# Clock.net
KiCad netlist of a schematic drawn in Altium Designer
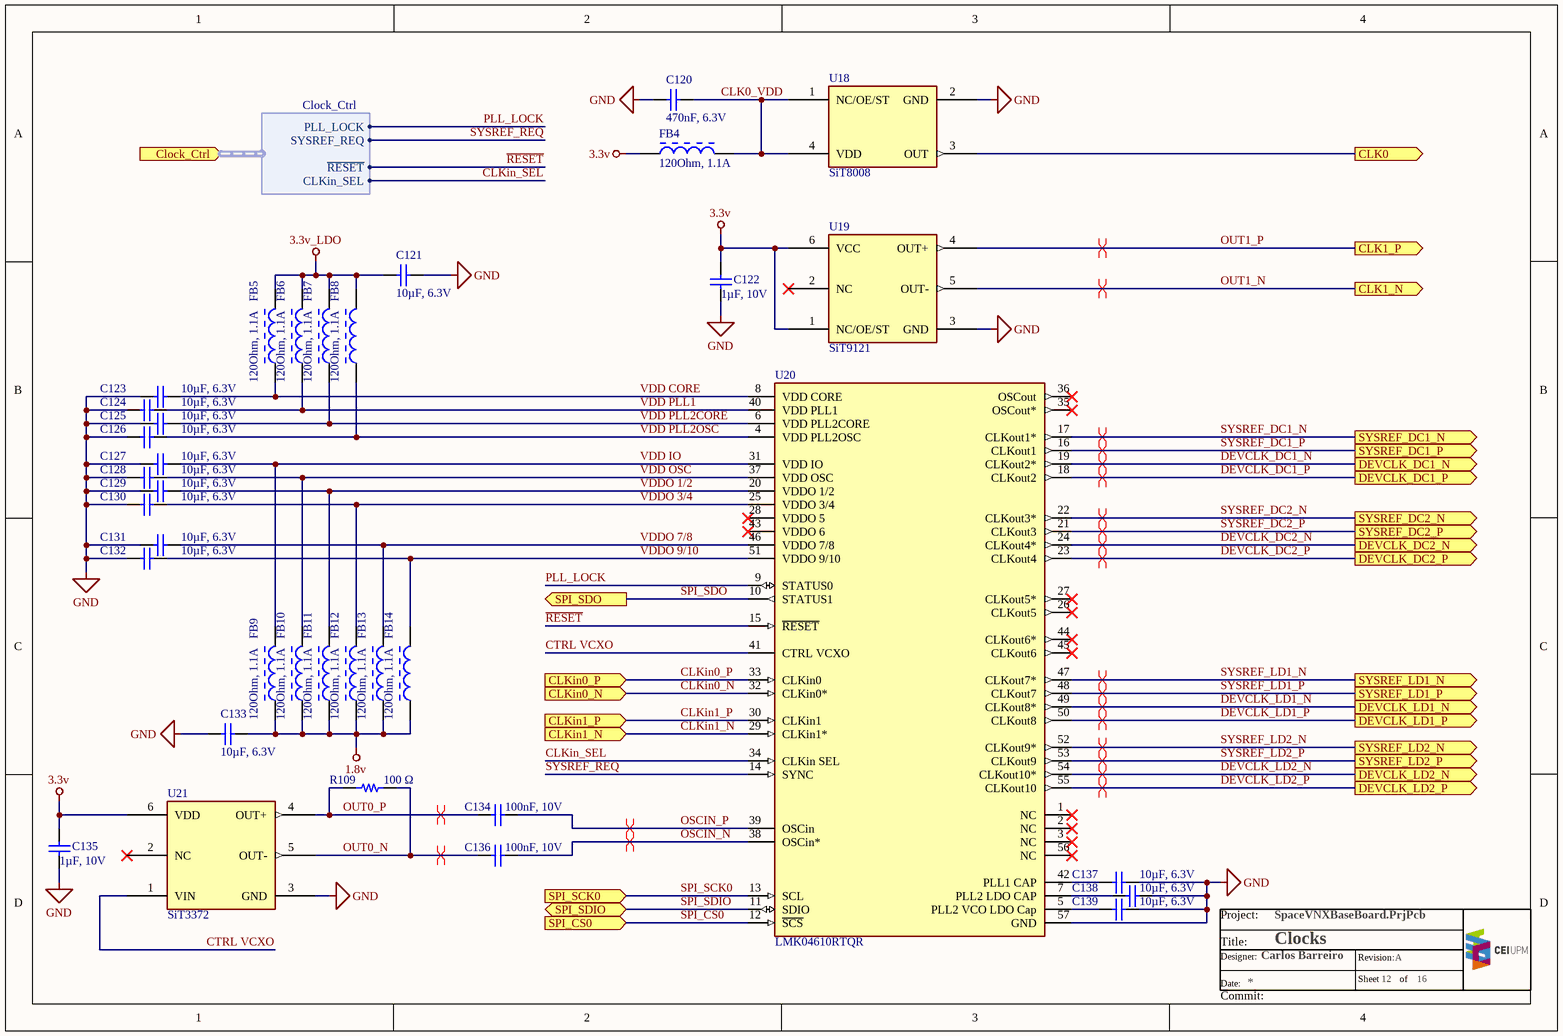
[diagram p0: Clock.SchDoc]

(export (version "E")
  (design (tool "Eeschema 10.0.6"))
  (components
    (comp (ref "C120")
      (value "470nF, 6.3V")
      (footprint "WURTH_WCAP-CSGP_0402")
      (description "WCAP-CSGP Multilayer Ceramic Chip Capacitor, General Purpose, size 0402, X5R, 470nF, 6.3V")
      (fields
        (field (name "MANUFACTURER PART NUMBER") "885012105004")
        (field (name "MANUFACTURER") "Wurth Elektronik")
      )
      (libsource (lib "SpaceVNX") (part "885012105004"))
    )
    (comp (ref "C121")
      (value "10µF, 6.3V")
      (footprint "WURTH_WCAP-CSGP_0402")
      (description "WCAP-CSGP Multilayer Ceramic Chip Capacitor, General Purpose, size 0402, X5R, 10uF, 6.3V")
      (fields
        (field (name "MANUFACTURER PART NUMBER") "885012105020")
        (field (name "MANUFACTURER") "Wurth Elektronik")
      )
      (libsource (lib "SpaceVNX") (part "885012105020"))
    )
    (comp (ref "C122")
      (value "1µF, 10V")
      (footprint "WURTH_WCAP-CSGP_0402")
      (description "WCAP-CSGP Multilayer Ceramic Chip Capacitor, General Purpose, size 0402, X5R, 1uF, 10V")
      (fields
        (field (name "MANUFACTURER PART NUMBER") "885012105012")
        (field (name "MANUFACTURER") "Wurth Elektronik")
      )
      (libsource (lib "SpaceVNX") (part "885012105012"))
    )
    (comp (ref "C123")
      (value "10µF, 6.3V")
      (footprint "WURTH_WCAP-CSGP_0402")
      (description "WCAP-CSGP Multilayer Ceramic Chip Capacitor, General Purpose, size 0402, X5R, 10uF, 6.3V")
      (fields
        (field (name "MANUFACTURER PART NUMBER") "885012105020")
        (field (name "MANUFACTURER") "Wurth Elektronik")
      )
      (libsource (lib "SpaceVNX") (part "885012105020"))
    )
    (comp (ref "C124")
      (value "10µF, 6.3V")
      (footprint "WURTH_WCAP-CSGP_0402")
      (description "WCAP-CSGP Multilayer Ceramic Chip Capacitor, General Purpose, size 0402, X5R, 10uF, 6.3V")
      (fields
        (field (name "MANUFACTURER PART NUMBER") "885012105020")
        (field (name "MANUFACTURER") "Wurth Elektronik")
      )
      (libsource (lib "SpaceVNX") (part "885012105020"))
    )
    (comp (ref "C125")
      (value "10µF, 6.3V")
      (footprint "WURTH_WCAP-CSGP_0402")
      (description "WCAP-CSGP Multilayer Ceramic Chip Capacitor, General Purpose, size 0402, X5R, 10uF, 6.3V")
      (fields
        (field (name "MANUFACTURER PART NUMBER") "885012105020")
        (field (name "MANUFACTURER") "Wurth Elektronik")
      )
      (libsource (lib "SpaceVNX") (part "885012105020"))
    )
    (comp (ref "C126")
      (value "10µF, 6.3V")
      (footprint "WURTH_WCAP-CSGP_0402")
      (description "WCAP-CSGP Multilayer Ceramic Chip Capacitor, General Purpose, size 0402, X5R, 10uF, 6.3V")
      (fields
        (field (name "MANUFACTURER PART NUMBER") "885012105020")
        (field (name "MANUFACTURER") "Wurth Elektronik")
      )
      (libsource (lib "SpaceVNX") (part "885012105020"))
    )
    (comp (ref "C127")
      (value "10µF, 6.3V")
      (footprint "WURTH_WCAP-CSGP_0402")
      (description "WCAP-CSGP Multilayer Ceramic Chip Capacitor, General Purpose, size 0402, X5R, 10uF, 6.3V")
      (fields
        (field (name "MANUFACTURER PART NUMBER") "885012105020")
        (field (name "MANUFACTURER") "Wurth Elektronik")
      )
      (libsource (lib "SpaceVNX") (part "885012105020"))
    )
    (comp (ref "C128")
      (value "10µF, 6.3V")
      (footprint "WURTH_WCAP-CSGP_0402")
      (description "WCAP-CSGP Multilayer Ceramic Chip Capacitor, General Purpose, size 0402, X5R, 10uF, 6.3V")
      (fields
        (field (name "MANUFACTURER PART NUMBER") "885012105020")
        (field (name "MANUFACTURER") "Wurth Elektronik")
      )
      (libsource (lib "SpaceVNX") (part "885012105020"))
    )
    (comp (ref "C129")
      (value "10µF, 6.3V")
      (footprint "WURTH_WCAP-CSGP_0402")
      (description "WCAP-CSGP Multilayer Ceramic Chip Capacitor, General Purpose, size 0402, X5R, 10uF, 6.3V")
      (fields
        (field (name "MANUFACTURER PART NUMBER") "885012105020")
        (field (name "MANUFACTURER") "Wurth Elektronik")
      )
      (libsource (lib "SpaceVNX") (part "885012105020"))
    )
    (comp (ref "C130")
      (value "10µF, 6.3V")
      (footprint "WURTH_WCAP-CSGP_0402")
      (description "WCAP-CSGP Multilayer Ceramic Chip Capacitor, General Purpose, size 0402, X5R, 10uF, 6.3V")
      (fields
        (field (name "MANUFACTURER PART NUMBER") "885012105020")
        (field (name "MANUFACTURER") "Wurth Elektronik")
      )
      (libsource (lib "SpaceVNX") (part "885012105020"))
    )
    (comp (ref "C131")
      (value "10µF, 6.3V")
      (footprint "WURTH_WCAP-CSGP_0402")
      (description "WCAP-CSGP Multilayer Ceramic Chip Capacitor, General Purpose, size 0402, X5R, 10uF, 6.3V")
      (fields
        (field (name "MANUFACTURER PART NUMBER") "885012105020")
        (field (name "MANUFACTURER") "Wurth Elektronik")
      )
      (libsource (lib "SpaceVNX") (part "885012105020"))
    )
    (comp (ref "C132")
      (value "10µF, 6.3V")
      (footprint "WURTH_WCAP-CSGP_0402")
      (description "WCAP-CSGP Multilayer Ceramic Chip Capacitor, General Purpose, size 0402, X5R, 10uF, 6.3V")
      (fields
        (field (name "MANUFACTURER PART NUMBER") "885012105020")
        (field (name "MANUFACTURER") "Wurth Elektronik")
      )
      (libsource (lib "SpaceVNX") (part "885012105020"))
    )
    (comp (ref "C133")
      (value "10µF, 6.3V")
      (footprint "WURTH_WCAP-CSGP_0402")
      (description "WCAP-CSGP Multilayer Ceramic Chip Capacitor, General Purpose, size 0402, X5R, 10uF, 6.3V")
      (fields
        (field (name "MANUFACTURER PART NUMBER") "885012105020")
        (field (name "MANUFACTURER") "Wurth Elektronik")
      )
      (libsource (lib "SpaceVNX") (part "885012105020"))
    )
    (comp (ref "C134")
      (value "100nF, 10V")
      (footprint "WURTH_WCAP-CSGP_0402")
      (description "WCAP-CSGP Multilayer Ceramic Chip Capacitor, General Purpose, size 0402, X7R, 100nF, 10V")
      (fields
        (field (name "MANUFACTURER PART NUMBER") "885012205018")
        (field (name "MANUFACTURER") "Wurth Elektronik")
      )
      (libsource (lib "SpaceVNX") (part "885012205018"))
    )
    (comp (ref "C135")
      (value "1µF, 10V")
      (footprint "WURTH_WCAP-CSGP_0402")
      (description "WCAP-CSGP Multilayer Ceramic Chip Capacitor, General Purpose, size 0402, X5R, 1uF, 10V")
      (fields
        (field (name "MANUFACTURER PART NUMBER") "885012105012")
        (field (name "MANUFACTURER") "Wurth Elektronik")
      )
      (libsource (lib "SpaceVNX") (part "885012105012"))
    )
    (comp (ref "C136")
      (value "100nF, 10V")
      (footprint "WURTH_WCAP-CSGP_0402")
      (description "WCAP-CSGP Multilayer Ceramic Chip Capacitor, General Purpose, size 0402, X7R, 100nF, 10V")
      (fields
        (field (name "MANUFACTURER PART NUMBER") "885012205018")
        (field (name "MANUFACTURER") "Wurth Elektronik")
      )
      (libsource (lib "SpaceVNX") (part "885012205018"))
    )
    (comp (ref "C137")
      (value "10µF, 6.3V")
      (footprint "WURTH_WCAP-CSGP_0402")
      (description "WCAP-CSGP Multilayer Ceramic Chip Capacitor, General Purpose, size 0402, X5R, 10uF, 6.3V")
      (fields
        (field (name "MANUFACTURER PART NUMBER") "885012105020")
        (field (name "MANUFACTURER") "Wurth Elektronik")
      )
      (libsource (lib "SpaceVNX") (part "885012105020"))
    )
    (comp (ref "C138")
      (value "10µF, 6.3V")
      (footprint "WURTH_WCAP-CSGP_0402")
      (description "WCAP-CSGP Multilayer Ceramic Chip Capacitor, General Purpose, size 0402, X5R, 10uF, 6.3V")
      (fields
        (field (name "MANUFACTURER PART NUMBER") "885012105020")
        (field (name "MANUFACTURER") "Wurth Elektronik")
      )
      (libsource (lib "SpaceVNX") (part "885012105020"))
    )
    (comp (ref "C139")
      (value "10µF, 6.3V")
      (footprint "WURTH_WCAP-CSGP_0402")
      (description "WCAP-CSGP Multilayer Ceramic Chip Capacitor, General Purpose, size 0402, X5R, 10uF, 6.3V")
      (fields
        (field (name "MANUFACTURER PART NUMBER") "885012105020")
        (field (name "MANUFACTURER") "Wurth Elektronik")
      )
      (libsource (lib "SpaceVNX") (part "885012105020"))
    )
    (comp (ref "FB4")
      (value "120Ohm, 1.1A")
      (footprint "WURTH-CBF_0402")
      (description "WE-CBF SMT EMI Suppression Ferrite Bead, size 0402, 120Ohm, 1.1A")
      (fields
        (field (name "MANUFACTURER PART NUMBER") "74279271")
        (field (name "MANUFACTURER") "Wurth Elektronik")
      )
      (libsource (lib "SpaceVNX") (part "74279271"))
    )
    (comp (ref "FB5")
      (value "120Ohm, 1.1A")
      (footprint "WURTH-CBF_0402")
      (description "WE-CBF SMT EMI Suppression Ferrite Bead, size 0402, 120Ohm, 1.1A")
      (fields
        (field (name "MANUFACTURER PART NUMBER") "74279271")
        (field (name "MANUFACTURER") "Wurth Elektronik")
      )
      (libsource (lib "SpaceVNX") (part "74279271"))
    )
    (comp (ref "FB6")
      (value "120Ohm, 1.1A")
      (footprint "WURTH-CBF_0402")
      (description "WE-CBF SMT EMI Suppression Ferrite Bead, size 0402, 120Ohm, 1.1A")
      (fields
        (field (name "MANUFACTURER PART NUMBER") "74279271")
        (field (name "MANUFACTURER") "Wurth Elektronik")
      )
      (libsource (lib "SpaceVNX") (part "74279271"))
    )
    (comp (ref "FB7")
      (value "120Ohm, 1.1A")
      (footprint "WURTH-CBF_0402")
      (description "WE-CBF SMT EMI Suppression Ferrite Bead, size 0402, 120Ohm, 1.1A")
      (fields
        (field (name "MANUFACTURER PART NUMBER") "74279271")
        (field (name "MANUFACTURER") "Wurth Elektronik")
      )
      (libsource (lib "SpaceVNX") (part "74279271"))
    )
    (comp (ref "FB8")
      (value "120Ohm, 1.1A")
      (footprint "WURTH-CBF_0402")
      (description "WE-CBF SMT EMI Suppression Ferrite Bead, size 0402, 120Ohm, 1.1A")
      (fields
        (field (name "MANUFACTURER PART NUMBER") "74279271")
        (field (name "MANUFACTURER") "Wurth Elektronik")
      )
      (libsource (lib "SpaceVNX") (part "74279271"))
    )
    (comp (ref "FB9")
      (value "120Ohm, 1.1A")
      (footprint "WURTH-CBF_0402")
      (description "WE-CBF SMT EMI Suppression Ferrite Bead, size 0402, 120Ohm, 1.1A")
      (fields
        (field (name "MANUFACTURER PART NUMBER") "74279271")
        (field (name "MANUFACTURER") "Wurth Elektronik")
      )
      (libsource (lib "SpaceVNX") (part "74279271"))
    )
    (comp (ref "FB10")
      (value "120Ohm, 1.1A")
      (footprint "WURTH-CBF_0402")
      (description "WE-CBF SMT EMI Suppression Ferrite Bead, size 0402, 120Ohm, 1.1A")
      (fields
        (field (name "MANUFACTURER PART NUMBER") "74279271")
        (field (name "MANUFACTURER") "Wurth Elektronik")
      )
      (libsource (lib "SpaceVNX") (part "74279271"))
    )
    (comp (ref "FB11")
      (value "120Ohm, 1.1A")
      (footprint "WURTH-CBF_0402")
      (description "WE-CBF SMT EMI Suppression Ferrite Bead, size 0402, 120Ohm, 1.1A")
      (fields
        (field (name "MANUFACTURER PART NUMBER") "74279271")
        (field (name "MANUFACTURER") "Wurth Elektronik")
      )
      (libsource (lib "SpaceVNX") (part "74279271"))
    )
    (comp (ref "FB12")
      (value "120Ohm, 1.1A")
      (footprint "WURTH-CBF_0402")
      (description "WE-CBF SMT EMI Suppression Ferrite Bead, size 0402, 120Ohm, 1.1A")
      (fields
        (field (name "MANUFACTURER PART NUMBER") "74279271")
        (field (name "MANUFACTURER") "Wurth Elektronik")
      )
      (libsource (lib "SpaceVNX") (part "74279271"))
    )
    (comp (ref "FB13")
      (value "120Ohm, 1.1A")
      (footprint "WURTH-CBF_0402")
      (description "WE-CBF SMT EMI Suppression Ferrite Bead, size 0402, 120Ohm, 1.1A")
      (fields
        (field (name "MANUFACTURER PART NUMBER") "74279271")
        (field (name "MANUFACTURER") "Wurth Elektronik")
      )
      (libsource (lib "SpaceVNX") (part "74279271"))
    )
    (comp (ref "FB14")
      (value "120Ohm, 1.1A")
      (footprint "WURTH-CBF_0402")
      (description "WE-CBF SMT EMI Suppression Ferrite Bead, size 0402, 120Ohm, 1.1A")
      (fields
        (field (name "MANUFACTURER PART NUMBER") "74279271")
        (field (name "MANUFACTURER") "Wurth Elektronik")
      )
      (libsource (lib "SpaceVNX") (part "74279271"))
    )
    (comp (ref "R109")
      (value "100 Ω")
      (footprint "PANASONIC_ERJ2G_0402")
      (description "General Purpose Thick Film Chip Resistors")
      (fields (field (name "MANUFACTURER") "Panasonic"))
      (libsource (lib "SpaceVNX") (part "ERJ2GEJ101X"))
    )
    (comp (ref "U18")
      (value "SiT8008")
      (footprint "SiTime_5032_4")
      (libsource (lib "SpaceVNX") (part "SiT8008"))
    )
    (comp (ref "U19")
      (value "SiT9121")
      (footprint "SiTime_5032_6")
      (description "Programmable differential oscillator that supports LVPECL and LVDS output.")
      (libsource (lib "SpaceVNX") (part "SiT9121"))
    )
    (comp (ref "U20")
      (value "LMK04610RTQR")
      (footprint "TEXAS_VQFN56")
      (description "Ultra low-noise and low power JESD204B compliant clock jitter cleaner with dual PLLs.")
      (libsource (lib "SpaceVNX") (part "LMK04610RTQR"))
    )
    (comp (ref "U21")
      (value "SiT3372")
      (footprint "SiTime_5032_6")
      (description "Ultra-low Jitter Differential VCXO.")
      (libsource (lib "SpaceVNX") (part "SiT3372"))
    )
  )
  (nets
    (net (code "2") (name "/CLK0") (class "Default")
      (node (ref "U18") (pin "3") (pinfunction "OUT_3") (pintype "output"))
    )
    (net (code "3") (name "/CLK0_VDD") (class "Default")
      (node (ref "C120") (pin "2") (pinfunction "2_2") (pintype "passive"))
      (node (ref "FB4") (pin "1") (pinfunction "1_1") (pintype "passive"))
      (node (ref "U18") (pin "1") (pinfunction "NC/OE/ST_1") (pintype "passive"))
      (node (ref "U18") (pin "4") (pinfunction "VDD_4") (pintype "passive"))
    )
    (net (code "4") (name "/CLKin0_N") (class "Default")
      (node (ref "U20") (pin "32") (pinfunction "CLKin0*_32") (pintype "input"))
    )
    (net (code "5") (name "/CLKin0_P") (class "Default")
      (node (ref "U20") (pin "33") (pinfunction "CLKin0_33") (pintype "input"))
    )
    (net (code "6") (name "/CLKin1_N") (class "Default")
      (node (ref "U20") (pin "29") (pinfunction "CLKin1*_29") (pintype "input"))
    )
    (net (code "7") (name "/CLKin1_P") (class "Default")
      (node (ref "U20") (pin "30") (pinfunction "CLKin1_30") (pintype "input"))
    )
    (net (code "8") (name "/CLKin_SEL") (class "Default")
      (node (ref "U20") (pin "34") (pinfunction "CLKin_SEL_34") (pintype "input"))
    )
    (net (code "9") (name "/CTRL VCXO") (class "Default")
      (node (ref "U20") (pin "41") (pinfunction "CTRL_VCXO_41") (pintype "power_in"))
      (node (ref "U21") (pin "1") (pinfunction "VIN_1") (pintype "passive"))
    )
    (net (code "10") (name "/DEVCLK_DC1_N") (class "Default")
      (node (ref "U20") (pin "19") (pinfunction "CLKout2*_19") (pintype "output"))
    )
    (net (code "11") (name "/DEVCLK_DC1_P") (class "Default")
      (node (ref "U20") (pin "18") (pinfunction "CLKout2_18") (pintype "output"))
    )
    (net (code "12") (name "/DEVCLK_DC2_N") (class "Default")
      (node (ref "U20") (pin "24") (pinfunction "CLKout4*_24") (pintype "output"))
    )
    (net (code "13") (name "/DEVCLK_DC2_P") (class "Default")
      (node (ref "U20") (pin "23") (pinfunction "CLKout4_23") (pintype "output"))
    )
    (net (code "14") (name "/DEVCLK_LD1_N") (class "Default")
      (node (ref "U20") (pin "49") (pinfunction "CLKout8*_49") (pintype "output"))
    )
    (net (code "15") (name "/DEVCLK_LD1_P") (class "Default")
      (node (ref "U20") (pin "50") (pinfunction "CLKout8_50") (pintype "output"))
    )
    (net (code "16") (name "/DEVCLK_LD2_N") (class "Default")
      (node (ref "U20") (pin "54") (pinfunction "CLKout10*_54") (pintype "output"))
    )
    (net (code "17") (name "/DEVCLK_LD2_P") (class "Default")
      (node (ref "U20") (pin "55") (pinfunction "CLKout10_55") (pintype "output"))
    )
    (net (code "18") (name "/OSCIN_N") (class "Default")
      (node (ref "C136") (pin "2") (pinfunction "2_2") (pintype "passive"))
      (node (ref "U20") (pin "38") (pinfunction "OSCin*_38") (pintype "passive"))
    )
    (net (code "19") (name "/OSCIN_P") (class "Default")
      (node (ref "C134") (pin "2") (pinfunction "2_2") (pintype "passive"))
      (node (ref "U20") (pin "39") (pinfunction "OSCin_39") (pintype "passive"))
    )
    (net (code "20") (name "/OUT0_N") (class "Default")
      (node (ref "C136") (pin "1") (pinfunction "1_1") (pintype "passive"))
      (node (ref "R109") (pin "2") (pinfunction "2_2") (pintype "passive"))
      (node (ref "U21") (pin "5") (pinfunction "OUT-_5") (pintype "output"))
    )
    (net (code "21") (name "/OUT0_P") (class "Default")
      (node (ref "C134") (pin "1") (pinfunction "1_1") (pintype "passive"))
      (node (ref "R109") (pin "1") (pinfunction "1_1") (pintype "passive"))
      (node (ref "U21") (pin "4") (pinfunction "OUT+_4") (pintype "output"))
    )
    (net (code "22") (name "/OUT1_N") (class "Default")
      (node (ref "U19") (pin "5") (pinfunction "OUT-_5") (pintype "output"))
    )
    (net (code "23") (name "/OUT1_P") (class "Default")
      (node (ref "U19") (pin "4") (pinfunction "OUT+_4") (pintype "output"))
    )
    (net (code "24") (name "/PLL_LOCK") (class "Default")
      (node (ref "U20") (pin "9") (pinfunction "STATUS0_9") (pintype "bidirectional"))
    )
    (net (code "25") (name "/SPI_CS0") (class "Default")
      (node (ref "U20") (pin "12") (pinfunction "~{SCS}_12") (pintype "input"))
    )
    (net (code "26") (name "/SPI_SCK0") (class "Default")
      (node (ref "U20") (pin "13") (pinfunction "SCL_13") (pintype "input"))
    )
    (net (code "27") (name "/SPI_SDIO") (class "Default")
      (node (ref "U20") (pin "11") (pinfunction "SDIO_11") (pintype "bidirectional"))
    )
    (net (code "28") (name "/SPI_SDO") (class "Default")
      (node (ref "U20") (pin "10") (pinfunction "STATUS1_10") (pintype "output"))
    )
    (net (code "29") (name "/SYSREF_DC1_N") (class "Default")
      (node (ref "U20") (pin "17") (pinfunction "CLKout1*_17") (pintype "output"))
    )
    (net (code "30") (name "/SYSREF_DC1_P") (class "Default")
      (node (ref "U20") (pin "16") (pinfunction "CLKout1_16") (pintype "output"))
    )
    (net (code "31") (name "/SYSREF_DC2_N") (class "Default")
      (node (ref "U20") (pin "22") (pinfunction "CLKout3*_22") (pintype "output"))
    )
    (net (code "32") (name "/SYSREF_DC2_P") (class "Default")
      (node (ref "U20") (pin "21") (pinfunction "CLKout3_21") (pintype "output"))
    )
    (net (code "33") (name "/SYSREF_LD1_N") (class "Default")
      (node (ref "U20") (pin "47") (pinfunction "CLKout7*_47") (pintype "output"))
    )
    (net (code "34") (name "/SYSREF_LD1_P") (class "Default")
      (node (ref "U20") (pin "48") (pinfunction "CLKout7_48") (pintype "output"))
    )
    (net (code "35") (name "/SYSREF_LD2_N") (class "Default")
      (node (ref "U20") (pin "52") (pinfunction "CLKout9*_52") (pintype "output"))
    )
    (net (code "36") (name "/SYSREF_LD2_P") (class "Default")
      (node (ref "U20") (pin "53") (pinfunction "CLKout9_53") (pintype "output"))
    )
    (net (code "37") (name "/SYSREF_REQ") (class "Default")
      (node (ref "U20") (pin "14") (pinfunction "SYNC_14") (pintype "input"))
    )
    (net (code "38") (name "/VDD CORE") (class "Default")
      (node (ref "C123") (pin "2") (pinfunction "2_2") (pintype "passive"))
      (node (ref "FB5") (pin "2") (pinfunction "2_2") (pintype "passive"))
      (node (ref "U20") (pin "8") (pinfunction "VDD_CORE_8") (pintype "power_in"))
    )
    (net (code "39") (name "/VDD IO") (class "Default")
      (node (ref "C127") (pin "2") (pinfunction "2_2") (pintype "passive"))
      (node (ref "FB9") (pin "1") (pinfunction "1_1") (pintype "passive"))
      (node (ref "U20") (pin "31") (pinfunction "VDD_IO_31") (pintype "power_in"))
    )
    (net (code "40") (name "/VDD OSC") (class "Default")
      (node (ref "C128") (pin "2") (pinfunction "2_2") (pintype "passive"))
      (node (ref "FB10") (pin "1") (pinfunction "1_1") (pintype "passive"))
      (node (ref "U20") (pin "37") (pinfunction "VDD_OSC_37") (pintype "power_in"))
    )
    (net (code "41") (name "/VDD PLL1") (class "Default")
      (node (ref "C124") (pin "2") (pinfunction "2_2") (pintype "passive"))
      (node (ref "FB6") (pin "2") (pinfunction "2_2") (pintype "passive"))
      (node (ref "U20") (pin "40") (pinfunction "VDD_PLL1_40") (pintype "power_in"))
    )
    (net (code "42") (name "/VDD PLL2CORE") (class "Default")
      (node (ref "C125") (pin "2") (pinfunction "2_2") (pintype "passive"))
      (node (ref "FB7") (pin "2") (pinfunction "2_2") (pintype "passive"))
      (node (ref "U20") (pin "6") (pinfunction "VDD_PLL2CORE_6") (pintype "power_in"))
    )
    (net (code "43") (name "/VDD PLL2OSC") (class "Default")
      (node (ref "C126") (pin "2") (pinfunction "2_2") (pintype "passive"))
      (node (ref "FB8") (pin "2") (pinfunction "2_2") (pintype "passive"))
      (node (ref "U20") (pin "4") (pinfunction "VDD_PLL2OSC_4") (pintype "power_in"))
    )
    (net (code "44") (name "/VDDO 1{slash}2") (class "Default")
      (node (ref "C129") (pin "2") (pinfunction "2_2") (pintype "passive"))
      (node (ref "FB11") (pin "1") (pinfunction "1_1") (pintype "passive"))
      (node (ref "U20") (pin "20") (pinfunction "VDDO_1/2_20") (pintype "power_in"))
    )
    (net (code "45") (name "/VDDO 3{slash}4") (class "Default")
      (node (ref "C130") (pin "2") (pinfunction "2_2") (pintype "passive"))
      (node (ref "FB12") (pin "1") (pinfunction "1_1") (pintype "passive"))
      (node (ref "U20") (pin "25") (pinfunction "VDDO_3/4_25") (pintype "power_in"))
    )
    (net (code "46") (name "/VDDO 7{slash}8") (class "Default")
      (node (ref "C131") (pin "2") (pinfunction "2_2") (pintype "passive"))
      (node (ref "FB13") (pin "1") (pinfunction "1_1") (pintype "passive"))
      (node (ref "U20") (pin "46") (pinfunction "VDDO_7/8_46") (pintype "power_in"))
    )
    (net (code "47") (name "/VDDO 9{slash}10") (class "Default")
      (node (ref "C132") (pin "2") (pinfunction "2_2") (pintype "passive"))
      (node (ref "FB14") (pin "1") (pinfunction "1_1") (pintype "passive"))
      (node (ref "U20") (pin "51") (pinfunction "VDDO_9/10_51") (pintype "power_in"))
    )
    (net (code "49") (name "/~{RESET}") (class "Default")
      (node (ref "U20") (pin "15") (pinfunction "~{RESET}_15") (pintype "input"))
    )
    (net (code "50") (name "1.8v") (class "Default")
      (node (ref "C133") (pin "2") (pinfunction "2_2") (pintype "passive"))
      (node (ref "FB10") (pin "2") (pinfunction "2_2") (pintype "passive"))
      (node (ref "FB11") (pin "2") (pinfunction "2_2") (pintype "passive"))
      (node (ref "FB12") (pin "2") (pinfunction "2_2") (pintype "passive"))
      (node (ref "FB13") (pin "2") (pinfunction "2_2") (pintype "passive"))
      (node (ref "FB14") (pin "2") (pinfunction "2_2") (pintype "passive"))
      (node (ref "FB9") (pin "2") (pinfunction "2_2") (pintype "passive"))
    )
    (net (code "51") (name "3.3v") (class "Default")
      (node (ref "C122") (pin "2") (pinfunction "2_2") (pintype "passive"))
      (node (ref "C135") (pin "2") (pinfunction "2_2") (pintype "passive"))
      (node (ref "FB4") (pin "2") (pinfunction "2_2") (pintype "passive"))
      (node (ref "U19") (pin "1") (pinfunction "NC/OE/ST_1") (pintype "passive"))
      (node (ref "U19") (pin "6") (pinfunction "VCC_6") (pintype "passive"))
      (node (ref "U21") (pin "6") (pinfunction "VDD_6") (pintype "passive"))
    )
    (net (code "52") (name "3.3v_LDO") (class "Default")
      (node (ref "C121") (pin "1") (pinfunction "1_1") (pintype "passive"))
      (node (ref "FB5") (pin "1") (pinfunction "1_1") (pintype "passive"))
      (node (ref "FB6") (pin "1") (pinfunction "1_1") (pintype "passive"))
      (node (ref "FB7") (pin "1") (pinfunction "1_1") (pintype "passive"))
      (node (ref "FB8") (pin "1") (pinfunction "1_1") (pintype "passive"))
    )
    (net (code "53") (name "GND") (class "Default")
      (node (ref "C120") (pin "1") (pinfunction "1_1") (pintype "passive"))
      (node (ref "C121") (pin "2") (pinfunction "2_2") (pintype "passive"))
      (node (ref "C122") (pin "1") (pinfunction "1_1") (pintype "passive"))
      (node (ref "C123") (pin "1") (pinfunction "1_1") (pintype "passive"))
      (node (ref "C124") (pin "1") (pinfunction "1_1") (pintype "passive"))
      (node (ref "C125") (pin "1") (pinfunction "1_1") (pintype "passive"))
      (node (ref "C126") (pin "1") (pinfunction "1_1") (pintype "passive"))
      (node (ref "C127") (pin "1") (pinfunction "1_1") (pintype "passive"))
      (node (ref "C128") (pin "1") (pinfunction "1_1") (pintype "passive"))
      (node (ref "C129") (pin "1") (pinfunction "1_1") (pintype "passive"))
      (node (ref "C130") (pin "1") (pinfunction "1_1") (pintype "passive"))
      (node (ref "C131") (pin "1") (pinfunction "1_1") (pintype "passive"))
      (node (ref "C132") (pin "1") (pinfunction "1_1") (pintype "passive"))
      (node (ref "C133") (pin "1") (pinfunction "1_1") (pintype "passive"))
      (node (ref "C135") (pin "1") (pinfunction "1_1") (pintype "passive"))
      (node (ref "C137") (pin "2") (pinfunction "2_2") (pintype "passive"))
      (node (ref "C138") (pin "2") (pinfunction "2_2") (pintype "passive"))
      (node (ref "C139") (pin "2") (pinfunction "2_2") (pintype "passive"))
      (node (ref "U18") (pin "2") (pinfunction "GND_2") (pintype "passive"))
      (node (ref "U19") (pin "3") (pinfunction "GND_3") (pintype "passive"))
      (node (ref "U20") (pin "57") (pinfunction "GND_57") (pintype "power_in"))
      (node (ref "U21") (pin "3") (pinfunction "GND_3") (pintype "passive"))
    )
    (net (code "54") (name "Net-(U20-PLL1_CAP)") (class "Default")
      (node (ref "C137") (pin "1") (pinfunction "1_1") (pintype "passive"))
      (node (ref "U20") (pin "42") (pinfunction "PLL1_CAP_42") (pintype "passive"))
    )
    (net (code "55") (name "Net-(U20-PLL2_LDO_CAP)") (class "Default")
      (node (ref "C138") (pin "1") (pinfunction "1_1") (pintype "passive"))
      (node (ref "U20") (pin "7") (pinfunction "PLL2_LDO_CAP_7") (pintype "power_in"))
    )
    (net (code "56") (name "Net-(U20-PLL2_VCO_LDO_Cap)") (class "Default")
      (node (ref "C139") (pin "1") (pinfunction "1_1") (pintype "passive"))
      (node (ref "U20") (pin "5") (pinfunction "PLL2_VCO_LDO_Cap_5") (pintype "power_in"))
    )
    (net (code "57") (name "unconnected-(U19-NC-Pad2)") (class "Default")
      (node (ref "U19") (pin "2") (pinfunction "NC_2") (pintype "passive+no_connect"))
    )
    (net (code "58") (name "unconnected-(U20-CLKout5*-Pad27)") (class "Default")
      (node (ref "U20") (pin "27") (pinfunction "CLKout5*_27") (pintype "output+no_connect"))
    )
    (net (code "59") (name "unconnected-(U20-CLKout5-Pad26)") (class "Default")
      (node (ref "U20") (pin "26") (pinfunction "CLKout5_26") (pintype "output+no_connect"))
    )
    (net (code "60") (name "unconnected-(U20-CLKout6*-Pad44)") (class "Default")
      (node (ref "U20") (pin "44") (pinfunction "CLKout6*_44") (pintype "output+no_connect"))
    )
    (net (code "61") (name "unconnected-(U20-CLKout6-Pad45)") (class "Default")
      (node (ref "U20") (pin "45") (pinfunction "CLKout6_45") (pintype "output+no_connect"))
    )
    (net (code "62") (name "unconnected-(U20-NC-Pad1)") (class "Default")
      (node (ref "U20") (pin "1") (pinfunction "NC_1") (pintype "passive+no_connect"))
    )
    (net (code "63") (name "unconnected-(U20-NC-Pad2)") (class "Default")
      (node (ref "U20") (pin "2") (pinfunction "NC_2") (pintype "passive+no_connect"))
    )
    (net (code "64") (name "unconnected-(U20-NC-Pad3)") (class "Default")
      (node (ref "U20") (pin "3") (pinfunction "NC_3") (pintype "passive+no_connect"))
    )
    (net (code "65") (name "unconnected-(U20-NC-Pad56)") (class "Default")
      (node (ref "U20") (pin "56") (pinfunction "NC_56") (pintype "passive+no_connect"))
    )
    (net (code "66") (name "unconnected-(U20-OSCout*-Pad35)") (class "Default")
      (node (ref "U20") (pin "35") (pinfunction "OSCout*_35") (pintype "output+no_connect"))
    )
    (net (code "67") (name "unconnected-(U20-OSCout-Pad36)") (class "Default")
      (node (ref "U20") (pin "36") (pinfunction "OSCout_36") (pintype "output+no_connect"))
    )
    (net (code "68") (name "unconnected-(U20-VDDO_5-Pad28)") (class "Default")
      (node (ref "U20") (pin "28") (pinfunction "VDDO_5_28") (pintype "power_in+no_connect"))
    )
    (net (code "69") (name "unconnected-(U20-VDDO_6-Pad43)") (class "Default")
      (node (ref "U20") (pin "43") (pinfunction "VDDO_6_43") (pintype "power_in+no_connect"))
    )
    (net (code "70") (name "unconnected-(U21-NC-Pad2)") (class "Default")
      (node (ref "U21") (pin "2") (pinfunction "NC_2") (pintype "passive+no_connect"))
    )
  )
)
